# 08_-_PERIPHERALS.net
KiCad netlist of a schematic drawn in Altium Designer
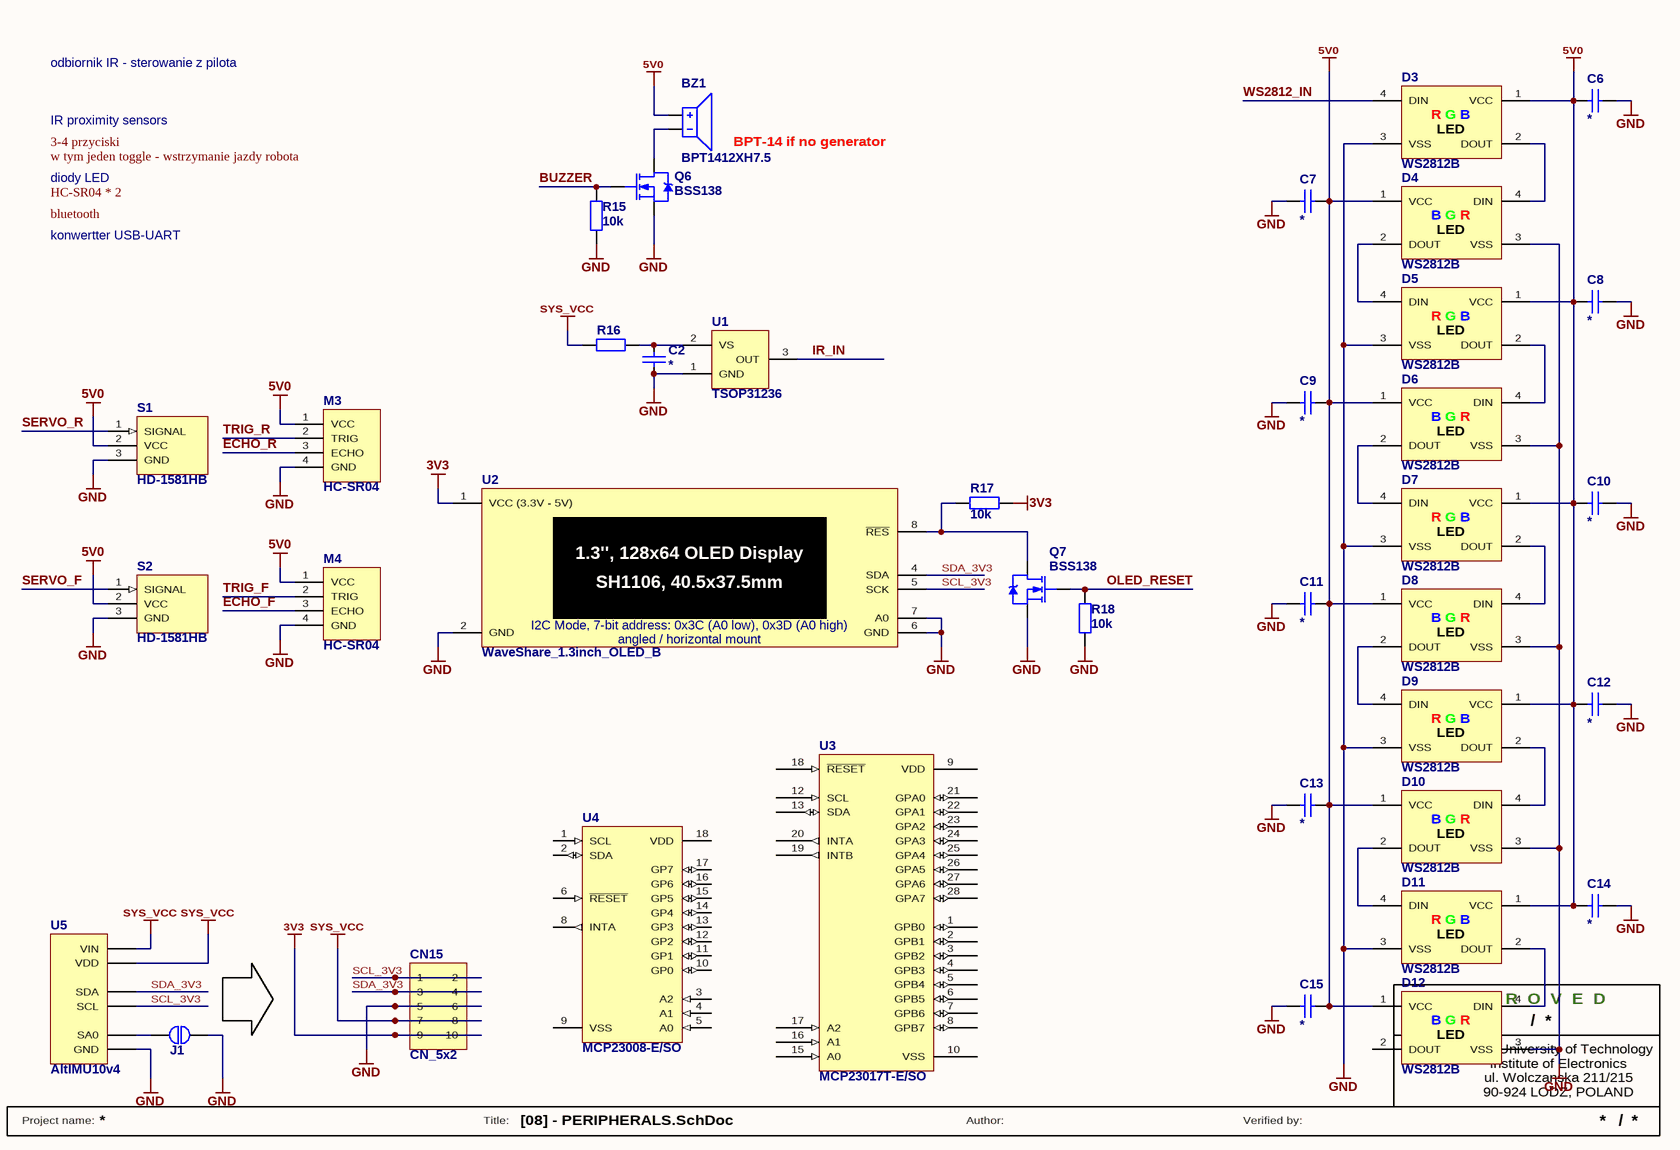
[diagram p0: [08] - PERIPHERALS.SchDoc]

(export (version "E")
  (design (tool "Eeschema 10.0.6"))
  (components
    (comp (ref "BZ1")
      (value "BPT1412XH7.5")
      (footprint "BUZ-13,8-7,6")
      (description "Piezoelectric Sound Transducer: 5Vp-p; 4kHz; O:14mm; with generator")
      (fields (field (name "PUBLISHER") "Altium Limited"))
      (libsource (lib "sounders") (part "BPT1412XH7.5"))
    )
    (comp (ref "C2")
      (value "*")
      (footprint "C1206")
      (description "Capacitor")
      (fields (field (name "ALTIUM_VALUE") "*"))
      (libsource (lib "capacitors") (part "Cap"))
    )
    (comp (ref "C6")
      (value "*")
      (footprint "C0805")
      (description "Capacitor")
      (fields (field (name "ALTIUM_VALUE") "*"))
      (libsource (lib "") (part "Cap_1"))
    )
    (comp (ref "C7")
      (value "*")
      (footprint "C0805")
      (description "Capacitor")
      (fields (field (name "ALTIUM_VALUE") "*"))
      (libsource (lib "") (part "Cap_1"))
    )
    (comp (ref "C8")
      (value "*")
      (footprint "C0805")
      (description "Capacitor")
      (fields (field (name "ALTIUM_VALUE") "*"))
      (libsource (lib "") (part "Cap_1"))
    )
    (comp (ref "C9")
      (value "*")
      (footprint "C0805")
      (description "Capacitor")
      (fields (field (name "ALTIUM_VALUE") "*"))
      (libsource (lib "") (part "Cap_1"))
    )
    (comp (ref "C10")
      (value "*")
      (footprint "C0805")
      (description "Capacitor")
      (fields (field (name "ALTIUM_VALUE") "*"))
      (libsource (lib "") (part "Cap_1"))
    )
    (comp (ref "C11")
      (value "*")
      (footprint "C0805")
      (description "Capacitor")
      (fields (field (name "ALTIUM_VALUE") "*"))
      (libsource (lib "") (part "Cap_1"))
    )
    (comp (ref "C12")
      (value "*")
      (footprint "C0805")
      (description "Capacitor")
      (fields (field (name "ALTIUM_VALUE") "*"))
      (libsource (lib "") (part "Cap_1"))
    )
    (comp (ref "C13")
      (value "*")
      (footprint "C0805")
      (description "Capacitor")
      (fields (field (name "ALTIUM_VALUE") "*"))
      (libsource (lib "") (part "Cap_1"))
    )
    (comp (ref "C14")
      (value "*")
      (footprint "C0805")
      (description "Capacitor")
      (fields (field (name "ALTIUM_VALUE") "*"))
      (libsource (lib "") (part "Cap_1"))
    )
    (comp (ref "C15")
      (value "*")
      (footprint "C0805")
      (description "Capacitor")
      (fields (field (name "ALTIUM_VALUE") "*"))
      (libsource (lib "") (part "Cap_1"))
    )
    (comp (ref "CN15")
      (value "CN_5x2")
      (footprint "GP_5x2H_F")
      (libsource (lib "goldpin_female") (part "CN_5x2"))
    )
    (comp (ref "D3")
      (value "WS2812B")
      (footprint "WS2812B")
      (description "Intelligent control LED integrated light source")
      (libsource (lib "leds") (part "WS2812B"))
    )
    (comp (ref "D4")
      (value "WS2812B")
      (footprint "WS2812B")
      (description "Intelligent control LED integrated light source")
      (libsource (lib "") (part "WS2812B_1"))
    )
    (comp (ref "D5")
      (value "WS2812B")
      (footprint "WS2812B")
      (description "Intelligent control LED integrated light source")
      (libsource (lib "leds") (part "WS2812B"))
    )
    (comp (ref "D6")
      (value "WS2812B")
      (footprint "WS2812B")
      (description "Intelligent control LED integrated light source")
      (libsource (lib "") (part "WS2812B_1"))
    )
    (comp (ref "D7")
      (value "WS2812B")
      (footprint "WS2812B")
      (description "Intelligent control LED integrated light source")
      (libsource (lib "leds") (part "WS2812B"))
    )
    (comp (ref "D8")
      (value "WS2812B")
      (footprint "WS2812B")
      (description "Intelligent control LED integrated light source")
      (libsource (lib "") (part "WS2812B_1"))
    )
    (comp (ref "D9")
      (value "WS2812B")
      (footprint "WS2812B")
      (description "Intelligent control LED integrated light source")
      (libsource (lib "leds") (part "WS2812B"))
    )
    (comp (ref "D10")
      (value "WS2812B")
      (footprint "WS2812B")
      (description "Intelligent control LED integrated light source")
      (libsource (lib "") (part "WS2812B_1"))
    )
    (comp (ref "D11")
      (value "WS2812B")
      (footprint "WS2812B")
      (description "Intelligent control LED integrated light source")
      (libsource (lib "leds") (part "WS2812B"))
    )
    (comp (ref "D12")
      (value "WS2812B")
      (footprint "WS2812B")
      (description "Intelligent control LED integrated light source")
      (libsource (lib "") (part "WS2812B_1"))
    )
    (comp (ref "J1")
      (value "Open")
      (footprint "JMP2_0603_NO")
      (description "Solder Jumper - Open")
      (libsource (lib "jumpers_and_circuit_brakers") (part "JUMPER2_NO"))
    )
    (comp (ref "M3")
      (value "HC-SR04")
      (footprint "HC-SR04")
      (libsource (lib "other_modules") (part "HC-SR04"))
    )
    (comp (ref "M4")
      (value "HC-SR04")
      (footprint "HC-SR04")
      (libsource (lib "other_modules") (part "HC-SR04"))
    )
    (comp (ref "Q6")
      (value "BSS138")
      (footprint "SOT-23")
      (description "N-Channel Enhancement Mode Vertical DMOS FET")
      (fields (field (name "PUBLISHER") "Altium Limited"))
      (libsource (lib "transistors_other") (part "BSS138"))
    )
    (comp (ref "Q7")
      (value "BSS138")
      (footprint "SOT-23")
      (description "N-Channel Enhancement Mode Vertical DMOS FET")
      (fields (field (name "PUBLISHER") "Altium Limited"))
      (libsource (lib "transistors_other") (part "BSS138"))
    )
    (comp (ref "R15")
      (value "10k")
      (footprint "R0603")
      (description "Resistor")
      (libsource (lib "resistors") (part "Res"))
    )
    (comp (ref "R16")
      (value "~")
      (footprint "R0603")
      (description "Resistor")
      (libsource (lib "") (part "Res_1"))
    )
    (comp (ref "R17")
      (value "10k")
      (footprint "R0603")
      (description "Resistor")
      (libsource (lib "") (part "Res_1"))
    )
    (comp (ref "R18")
      (value "10k")
      (footprint "R0603")
      (description "Resistor")
      (libsource (lib "resistors") (part "Res"))
    )
    (comp (ref "S1")
      (value "HD-1581HB")
      (footprint "HD-1581HB")
      (description "HD-1581HB Micro Servo")
      (libsource (lib "servos") (part "HD-1581HB"))
    )
    (comp (ref "S2")
      (value "HD-1581HB")
      (footprint "HD-1581HB")
      (description "HD-1581HB Micro Servo")
      (libsource (lib "servos") (part "HD-1581HB"))
    )
    (comp (ref "U1")
      (value "TSOP31236")
      (footprint "TSOP312 / TSOP314")
      (description "36kHz IR Receiver Module for Remote Control Systems")
      (libsource (lib "ir_receivers") (part "TSOP31236"))
    )
    (comp (ref "U2")
      (value "WaveShare_1.3inch_OLED_B")
      (footprint "WaveShare_1.3INCH_OLED")
      (description "DEP096032B-W OLED Display")
      (libsource (lib "oled_displays") (part "WaveShare_1.3inch_OLED"))
    )
    (comp (ref "U3")
      (value "MCP23017T-E/SO")
      (footprint "SO28")
      (description "16-Bit I/O Expander with Serial Interface I2C, Extended Temp, SO28 Package")
      (libsource (lib "io_expanders") (part "MCP23017T-E/SO"))
    )
    (comp (ref "U4")
      (value "MCP23008-E/SO")
      (footprint "SO18W")
      (description "8-Bit I/O Expander with Serial Interface I2C, 18-Pin SOIC Package")
      (libsource (lib "io_expanders") (part "MCP23008-E/SO"))
    )
    (comp (ref "U5")
      (value "AltIMU10v4")
      (footprint "AltIMU-10 v4")
      (description "Pololu Gyro, Accelerometer, Compass, and Altimeter (L3GD20H, LSM303D, and LPS25H Carrier)")
      (libsource (lib "mems_and_imu_modules") (part "AltIMU10v4"))
    )
  )
  (nets
    (net (code "2") (name "/BUZZER") (class "Default")
      (node (ref "Q6") (pin "1") (pinfunction "G_1") (pintype "passive"))
      (node (ref "R15") (pin "1") (pinfunction "1_1") (pintype "passive"))
    )
    (net (code "3") (name "/ECHO_F") (class "Default")
      (node (ref "M4") (pin "3") (pinfunction "ECHO_3") (pintype "power_in"))
    )
    (net (code "4") (name "/ECHO_R") (class "Default")
      (node (ref "M3") (pin "3") (pinfunction "ECHO_3") (pintype "power_in"))
    )
    (net (code "6") (name "/IR_IN") (class "Default")
      (node (ref "U1") (pin "3") (pinfunction "OUT_3") (pintype "passive"))
    )
    (net (code "7") (name "/OLED_RESET") (class "Default")
      (node (ref "Q7") (pin "1") (pinfunction "G_1") (pintype "passive"))
      (node (ref "R18") (pin "1") (pinfunction "1_1") (pintype "passive"))
    )
    (net (code "8") (name "/SCL_3V3") (class "Default")
      (node (ref "CN15") (pin "1") (pinfunction "1_1") (pintype "passive"))
      (node (ref "CN15") (pin "2") (pinfunction "2_2") (pintype "passive"))
      (node (ref "U2") (pin "5") (pinfunction "SCK_5") (pintype "passive"))
      (node (ref "U5") (pin "6") (pinfunction "SCL_6") (pintype "passive"))
    )
    (net (code "9") (name "/SDA_3V3") (class "Default")
      (node (ref "CN15") (pin "3") (pinfunction "3_3") (pintype "passive"))
      (node (ref "CN15") (pin "4") (pinfunction "4_4") (pintype "passive"))
      (node (ref "U2") (pin "4") (pinfunction "SDA_4") (pintype "passive"))
      (node (ref "U5") (pin "5") (pinfunction "SDA_5") (pintype "passive"))
    )
    (net (code "10") (name "/SERVO_F") (class "Default")
      (node (ref "S2") (pin "1") (pinfunction "SIGNAL_1") (pintype "input"))
    )
    (net (code "11") (name "/SERVO_R") (class "Default")
      (node (ref "S1") (pin "1") (pinfunction "SIGNAL_1") (pintype "input"))
    )
    (net (code "12") (name "/TRIG_F") (class "Default")
      (node (ref "M4") (pin "2") (pinfunction "TRIG_2") (pintype "power_in"))
    )
    (net (code "13") (name "/TRIG_R") (class "Default")
      (node (ref "M3") (pin "2") (pinfunction "TRIG_2") (pintype "power_in"))
    )
    (net (code "14") (name "/WS2812_IN") (class "Default")
      (node (ref "D3") (pin "4") (pinfunction "DIN_4") (pintype "power_in"))
    )
    (net (code "17") (name "3V3") (class "Default")
      (node (ref "CN15") (pin "10") (pinfunction "10_10") (pintype "passive"))
      (node (ref "CN15") (pin "9") (pinfunction "9_9") (pintype "passive"))
      (node (ref "R17") (pin "2") (pinfunction "2_2") (pintype "passive"))
      (node (ref "U2") (pin "1") (pinfunction "VCC_(3.3V_-_5V)_1") (pintype "passive"))
    )
    (net (code "18") (name "5V0") (class "Default")
      (node (ref "BZ1") (pin "1") (pinfunction "1_1") (pintype "passive"))
      (node (ref "C10") (pin "1") (pinfunction "1_1") (pintype "passive"))
      (node (ref "C11") (pin "2") (pinfunction "2_2") (pintype "passive"))
      (node (ref "C12") (pin "1") (pinfunction "1_1") (pintype "passive"))
      (node (ref "C13") (pin "2") (pinfunction "2_2") (pintype "passive"))
      (node (ref "C14") (pin "1") (pinfunction "1_1") (pintype "passive"))
      (node (ref "C15") (pin "2") (pinfunction "2_2") (pintype "passive"))
      (node (ref "C6") (pin "1") (pinfunction "1_1") (pintype "passive"))
      (node (ref "C7") (pin "2") (pinfunction "2_2") (pintype "passive"))
      (node (ref "C8") (pin "1") (pinfunction "1_1") (pintype "passive"))
      (node (ref "C9") (pin "2") (pinfunction "2_2") (pintype "passive"))
      (node (ref "D10") (pin "1") (pinfunction "VCC_1") (pintype "power_in"))
      (node (ref "D11") (pin "1") (pinfunction "VCC_1") (pintype "power_in"))
      (node (ref "D12") (pin "1") (pinfunction "VCC_1") (pintype "power_in"))
      (node (ref "D3") (pin "1") (pinfunction "VCC_1") (pintype "power_in"))
      (node (ref "D4") (pin "1") (pinfunction "VCC_1") (pintype "power_in"))
      (node (ref "D5") (pin "1") (pinfunction "VCC_1") (pintype "power_in"))
      (node (ref "D6") (pin "1") (pinfunction "VCC_1") (pintype "power_in"))
      (node (ref "D7") (pin "1") (pinfunction "VCC_1") (pintype "power_in"))
      (node (ref "D8") (pin "1") (pinfunction "VCC_1") (pintype "power_in"))
      (node (ref "D9") (pin "1") (pinfunction "VCC_1") (pintype "power_in"))
      (node (ref "M3") (pin "1") (pinfunction "VCC_1") (pintype "power_in"))
      (node (ref "M4") (pin "1") (pinfunction "VCC_1") (pintype "power_in"))
      (node (ref "S1") (pin "2") (pinfunction "VCC_2") (pintype "power_in"))
      (node (ref "S2") (pin "2") (pinfunction "VCC_2") (pintype "power_in"))
    )
    (net (code "19") (name "GND") (class "Default")
      (node (ref "C10") (pin "2") (pinfunction "2_2") (pintype "passive"))
      (node (ref "C11") (pin "1") (pinfunction "1_1") (pintype "passive"))
      (node (ref "C12") (pin "2") (pinfunction "2_2") (pintype "passive"))
      (node (ref "C13") (pin "1") (pinfunction "1_1") (pintype "passive"))
      (node (ref "C14") (pin "2") (pinfunction "2_2") (pintype "passive"))
      (node (ref "C15") (pin "1") (pinfunction "1_1") (pintype "passive"))
      (node (ref "C2") (pin "1") (pinfunction "1_1") (pintype "passive"))
      (node (ref "C6") (pin "2") (pinfunction "2_2") (pintype "passive"))
      (node (ref "C7") (pin "1") (pinfunction "1_1") (pintype "passive"))
      (node (ref "C8") (pin "2") (pinfunction "2_2") (pintype "passive"))
      (node (ref "C9") (pin "1") (pinfunction "1_1") (pintype "passive"))
      (node (ref "CN15") (pin "5") (pinfunction "5_5") (pintype "passive"))
      (node (ref "CN15") (pin "6") (pinfunction "6_6") (pintype "passive"))
      (node (ref "D10") (pin "3") (pinfunction "VSS_3") (pintype "power_in"))
      (node (ref "D11") (pin "3") (pinfunction "VSS_3") (pintype "power_in"))
      (node (ref "D12") (pin "3") (pinfunction "VSS_3") (pintype "power_in"))
      (node (ref "D3") (pin "3") (pinfunction "VSS_3") (pintype "power_in"))
      (node (ref "D4") (pin "3") (pinfunction "VSS_3") (pintype "power_in"))
      (node (ref "D5") (pin "3") (pinfunction "VSS_3") (pintype "power_in"))
      (node (ref "D6") (pin "3") (pinfunction "VSS_3") (pintype "power_in"))
      (node (ref "D7") (pin "3") (pinfunction "VSS_3") (pintype "power_in"))
      (node (ref "D8") (pin "3") (pinfunction "VSS_3") (pintype "power_in"))
      (node (ref "D9") (pin "3") (pinfunction "VSS_3") (pintype "power_in"))
      (node (ref "J1") (pin "1") (pinfunction "1_1") (pintype "passive"))
      (node (ref "M3") (pin "4") (pinfunction "GND_4") (pintype "power_in"))
      (node (ref "M4") (pin "4") (pinfunction "GND_4") (pintype "power_in"))
      (node (ref "Q6") (pin "2") (pinfunction "S_2") (pintype "passive"))
      (node (ref "Q7") (pin "2") (pinfunction "S_2") (pintype "passive"))
      (node (ref "R15") (pin "2") (pinfunction "2_2") (pintype "passive"))
      (node (ref "R18") (pin "2") (pinfunction "2_2") (pintype "passive"))
      (node (ref "S1") (pin "3") (pinfunction "GND_3") (pintype "power_in"))
      (node (ref "S2") (pin "3") (pinfunction "GND_3") (pintype "power_in"))
      (node (ref "U1") (pin "1") (pinfunction "GND_1") (pintype "passive"))
      (node (ref "U2") (pin "2") (pinfunction "GND_2") (pintype "passive"))
      (node (ref "U2") (pin "6") (pinfunction "GND_6") (pintype "passive"))
      (node (ref "U2") (pin "7") (pinfunction "A0_7") (pintype "passive"))
      (node (ref "U5") (pin "1") (pinfunction "GND_1") (pintype "passive"))
    )
    (net (code "20") (name "Net-(D3-DOUT)") (class "Default")
      (node (ref "D3") (pin "2") (pinfunction "DOUT_2") (pintype "power_in"))
      (node (ref "D4") (pin "4") (pinfunction "DIN_4") (pintype "power_in"))
    )
    (net (code "21") (name "Net-(D4-DOUT)") (class "Default")
      (node (ref "D4") (pin "2") (pinfunction "DOUT_2") (pintype "power_in"))
      (node (ref "D5") (pin "4") (pinfunction "DIN_4") (pintype "power_in"))
    )
    (net (code "22") (name "Net-(D5-DOUT)") (class "Default")
      (node (ref "D5") (pin "2") (pinfunction "DOUT_2") (pintype "power_in"))
      (node (ref "D6") (pin "4") (pinfunction "DIN_4") (pintype "power_in"))
    )
    (net (code "23") (name "Net-(D6-DOUT)") (class "Default")
      (node (ref "D6") (pin "2") (pinfunction "DOUT_2") (pintype "power_in"))
      (node (ref "D7") (pin "4") (pinfunction "DIN_4") (pintype "power_in"))
    )
    (net (code "24") (name "Net-(D7-DOUT)") (class "Default")
      (node (ref "D7") (pin "2") (pinfunction "DOUT_2") (pintype "power_in"))
      (node (ref "D8") (pin "4") (pinfunction "DIN_4") (pintype "power_in"))
    )
    (net (code "25") (name "Net-(D8-DOUT)") (class "Default")
      (node (ref "D8") (pin "2") (pinfunction "DOUT_2") (pintype "power_in"))
      (node (ref "D9") (pin "4") (pinfunction "DIN_4") (pintype "power_in"))
    )
    (net (code "26") (name "Net-(D10-DIN)") (class "Default")
      (node (ref "D10") (pin "4") (pinfunction "DIN_4") (pintype "power_in"))
      (node (ref "D9") (pin "2") (pinfunction "DOUT_2") (pintype "power_in"))
    )
    (net (code "27") (name "Net-(D10-DOUT)") (class "Default")
      (node (ref "D10") (pin "2") (pinfunction "DOUT_2") (pintype "power_in"))
      (node (ref "D11") (pin "4") (pinfunction "DIN_4") (pintype "power_in"))
    )
    (net (code "28") (name "Net-(D11-DOUT)") (class "Default")
      (node (ref "D11") (pin "2") (pinfunction "DOUT_2") (pintype "power_in"))
      (node (ref "D12") (pin "4") (pinfunction "DIN_4") (pintype "power_in"))
    )
    (net (code "29") (name "Net-(Q6-D)") (class "Default")
      (node (ref "BZ1") (pin "2") (pinfunction "2_2") (pintype "passive"))
      (node (ref "Q6") (pin "3") (pinfunction "D_3") (pintype "passive"))
    )
    (net (code "30") (name "Net-(Q7-D)") (class "Default")
      (node (ref "Q7") (pin "3") (pinfunction "D_3") (pintype "passive"))
      (node (ref "R17") (pin "1") (pinfunction "1_1") (pintype "passive"))
      (node (ref "U2") (pin "8") (pinfunction "~{RES}_8") (pintype "passive"))
    )
    (net (code "31") (name "Net-(U1-VS)") (class "Default")
      (node (ref "C2") (pin "2") (pinfunction "2_2") (pintype "passive"))
      (node (ref "R16") (pin "2") (pinfunction "2_2") (pintype "passive"))
      (node (ref "U1") (pin "2") (pinfunction "VS_2") (pintype "passive"))
    )
    (net (code "32") (name "Net-(U5-SA0)") (class "Default")
      (node (ref "J1") (pin "2") (pinfunction "2_2") (pintype "passive"))
      (node (ref "U5") (pin "2") (pinfunction "SA0_2") (pintype "passive"))
    )
    (net (code "33") (name "SYS_VCC") (class "Default")
      (node (ref "CN15") (pin "7") (pinfunction "7_7") (pintype "passive"))
      (node (ref "CN15") (pin "8") (pinfunction "8_8") (pintype "passive"))
      (node (ref "R16") (pin "1") (pinfunction "1_1") (pintype "passive"))
      (node (ref "U5") (pin "3") (pinfunction "VIN_3") (pintype "passive"))
      (node (ref "U5") (pin "4") (pinfunction "VDD_4") (pintype "passive"))
    )
    (net (code "34") (name "unconnected-(D12-DOUT-Pad2)") (class "Default")
      (node (ref "D12") (pin "2") (pinfunction "DOUT_2") (pintype "power_in"))
    )
    (net (code "35") (name "unconnected-(U3-A0-Pad15)") (class "Default")
      (node (ref "U3") (pin "15") (pinfunction "A0_15") (pintype "input"))
    )
    (net (code "36") (name "unconnected-(U3-A1-Pad16)") (class "Default")
      (node (ref "U3") (pin "16") (pinfunction "A1_16") (pintype "input"))
    )
    (net (code "37") (name "unconnected-(U3-A2-Pad17)") (class "Default")
      (node (ref "U3") (pin "17") (pinfunction "A2_17") (pintype "input"))
    )
    (net (code "38") (name "unconnected-(U3-GPA0-Pad21)") (class "Default")
      (node (ref "U3") (pin "21") (pinfunction "GPA0_21") (pintype "bidirectional"))
    )
    (net (code "39") (name "unconnected-(U3-GPA1-Pad22)") (class "Default")
      (node (ref "U3") (pin "22") (pinfunction "GPA1_22") (pintype "bidirectional"))
    )
    (net (code "40") (name "unconnected-(U3-GPA2-Pad23)") (class "Default")
      (node (ref "U3") (pin "23") (pinfunction "GPA2_23") (pintype "bidirectional"))
    )
    (net (code "41") (name "unconnected-(U3-GPA3-Pad24)") (class "Default")
      (node (ref "U3") (pin "24") (pinfunction "GPA3_24") (pintype "bidirectional"))
    )
    (net (code "42") (name "unconnected-(U3-GPA4-Pad25)") (class "Default")
      (node (ref "U3") (pin "25") (pinfunction "GPA4_25") (pintype "bidirectional"))
    )
    (net (code "43") (name "unconnected-(U3-GPA5-Pad26)") (class "Default")
      (node (ref "U3") (pin "26") (pinfunction "GPA5_26") (pintype "bidirectional"))
    )
    (net (code "44") (name "unconnected-(U3-GPA6-Pad27)") (class "Default")
      (node (ref "U3") (pin "27") (pinfunction "GPA6_27") (pintype "bidirectional"))
    )
    (net (code "45") (name "unconnected-(U3-GPA7-Pad28)") (class "Default")
      (node (ref "U3") (pin "28") (pinfunction "GPA7_28") (pintype "bidirectional"))
    )
    (net (code "46") (name "unconnected-(U3-GPB0-Pad1)") (class "Default")
      (node (ref "U3") (pin "1") (pinfunction "GPB0_1") (pintype "bidirectional"))
    )
    (net (code "47") (name "unconnected-(U3-GPB1-Pad2)") (class "Default")
      (node (ref "U3") (pin "2") (pinfunction "GPB1_2") (pintype "bidirectional"))
    )
    (net (code "48") (name "unconnected-(U3-GPB2-Pad3)") (class "Default")
      (node (ref "U3") (pin "3") (pinfunction "GPB2_3") (pintype "bidirectional"))
    )
    (net (code "49") (name "unconnected-(U3-GPB3-Pad4)") (class "Default")
      (node (ref "U3") (pin "4") (pinfunction "GPB3_4") (pintype "bidirectional"))
    )
    (net (code "50") (name "unconnected-(U3-GPB4-Pad5)") (class "Default")
      (node (ref "U3") (pin "5") (pinfunction "GPB4_5") (pintype "bidirectional"))
    )
    (net (code "51") (name "unconnected-(U3-GPB5-Pad6)") (class "Default")
      (node (ref "U3") (pin "6") (pinfunction "GPB5_6") (pintype "bidirectional"))
    )
    (net (code "52") (name "unconnected-(U3-GPB6-Pad7)") (class "Default")
      (node (ref "U3") (pin "7") (pinfunction "GPB6_7") (pintype "bidirectional"))
    )
    (net (code "53") (name "unconnected-(U3-GPB7-Pad8)") (class "Default")
      (node (ref "U3") (pin "8") (pinfunction "GPB7_8") (pintype "bidirectional"))
    )
    (net (code "54") (name "unconnected-(U3-INTA-Pad20)") (class "Default")
      (node (ref "U3") (pin "20") (pinfunction "INTA_20") (pintype "output"))
    )
    (net (code "55") (name "unconnected-(U3-INTB-Pad19)") (class "Default")
      (node (ref "U3") (pin "19") (pinfunction "INTB_19") (pintype "output"))
    )
    (net (code "56") (name "unconnected-(U3-NC-Pad11)") (class "Default")
      (node (ref "U3") (pin "11") (pinfunction "NC_11") (pintype "passive"))
    )
    (net (code "57") (name "unconnected-(U3-NC-Pad14)") (class "Default")
      (node (ref "U3") (pin "14") (pinfunction "NC_14") (pintype "passive"))
    )
    (net (code "58") (name "unconnected-(U3-SCL-Pad12)") (class "Default")
      (node (ref "U3") (pin "12") (pinfunction "SCL_12") (pintype "input"))
    )
    (net (code "59") (name "unconnected-(U3-SDA-Pad13)") (class "Default")
      (node (ref "U3") (pin "13") (pinfunction "SDA_13") (pintype "bidirectional"))
    )
    (net (code "60") (name "unconnected-(U3-VDD-Pad9)") (class "Default")
      (node (ref "U3") (pin "9") (pinfunction "VDD_9") (pintype "power_in"))
    )
    (net (code "61") (name "unconnected-(U3-VSS-Pad10)") (class "Default")
      (node (ref "U3") (pin "10") (pinfunction "VSS_10") (pintype "power_in"))
    )
    (net (code "62") (name "unconnected-(U3-~{RESET}-Pad18)") (class "Default")
      (node (ref "U3") (pin "18") (pinfunction "~{RESET}_18") (pintype "input"))
    )
    (net (code "63") (name "unconnected-(U4-A0-Pad5)") (class "Default")
      (node (ref "U4") (pin "5") (pinfunction "A0_5") (pintype "input"))
    )
    (net (code "64") (name "unconnected-(U4-A1-Pad4)") (class "Default")
      (node (ref "U4") (pin "4") (pinfunction "A1_4") (pintype "input"))
    )
    (net (code "65") (name "unconnected-(U4-A2-Pad3)") (class "Default")
      (node (ref "U4") (pin "3") (pinfunction "A2_3") (pintype "input"))
    )
    (net (code "66") (name "unconnected-(U4-GP0-Pad10)") (class "Default")
      (node (ref "U4") (pin "10") (pinfunction "GP0_10") (pintype "bidirectional"))
    )
    (net (code "67") (name "unconnected-(U4-GP1-Pad11)") (class "Default")
      (node (ref "U4") (pin "11") (pinfunction "GP1_11") (pintype "bidirectional"))
    )
    (net (code "68") (name "unconnected-(U4-GP2-Pad12)") (class "Default")
      (node (ref "U4") (pin "12") (pinfunction "GP2_12") (pintype "bidirectional"))
    )
    (net (code "69") (name "unconnected-(U4-GP3-Pad13)") (class "Default")
      (node (ref "U4") (pin "13") (pinfunction "GP3_13") (pintype "bidirectional"))
    )
    (net (code "70") (name "unconnected-(U4-GP4-Pad14)") (class "Default")
      (node (ref "U4") (pin "14") (pinfunction "GP4_14") (pintype "bidirectional"))
    )
    (net (code "71") (name "unconnected-(U4-GP5-Pad15)") (class "Default")
      (node (ref "U4") (pin "15") (pinfunction "GP5_15") (pintype "bidirectional"))
    )
    (net (code "72") (name "unconnected-(U4-GP6-Pad16)") (class "Default")
      (node (ref "U4") (pin "16") (pinfunction "GP6_16") (pintype "bidirectional"))
    )
    (net (code "73") (name "unconnected-(U4-GP7-Pad17)") (class "Default")
      (node (ref "U4") (pin "17") (pinfunction "GP7_17") (pintype "bidirectional"))
    )
    (net (code "74") (name "unconnected-(U4-INTA-Pad8)") (class "Default")
      (node (ref "U4") (pin "8") (pinfunction "INTA_8") (pintype "output"))
    )
    (net (code "75") (name "unconnected-(U4-SCL-Pad1)") (class "Default")
      (node (ref "U4") (pin "1") (pinfunction "SCL_1") (pintype "input"))
    )
    (net (code "76") (name "unconnected-(U4-SDA-Pad2)") (class "Default")
      (node (ref "U4") (pin "2") (pinfunction "SDA_2") (pintype "bidirectional"))
    )
    (net (code "77") (name "unconnected-(U4-VDD-Pad18)") (class "Default")
      (node (ref "U4") (pin "18") (pinfunction "VDD_18") (pintype "power_in"))
    )
    (net (code "78") (name "unconnected-(U4-VSS-Pad9)") (class "Default")
      (node (ref "U4") (pin "9") (pinfunction "VSS_9") (pintype "power_in"))
    )
    (net (code "79") (name "unconnected-(U4-~{RESET}-Pad6)") (class "Default")
      (node (ref "U4") (pin "6") (pinfunction "~{RESET}_6") (pintype "input"))
    )
  )
)
